# light_brick.net
KiCad netlist of a schematic drawn in EAGLE
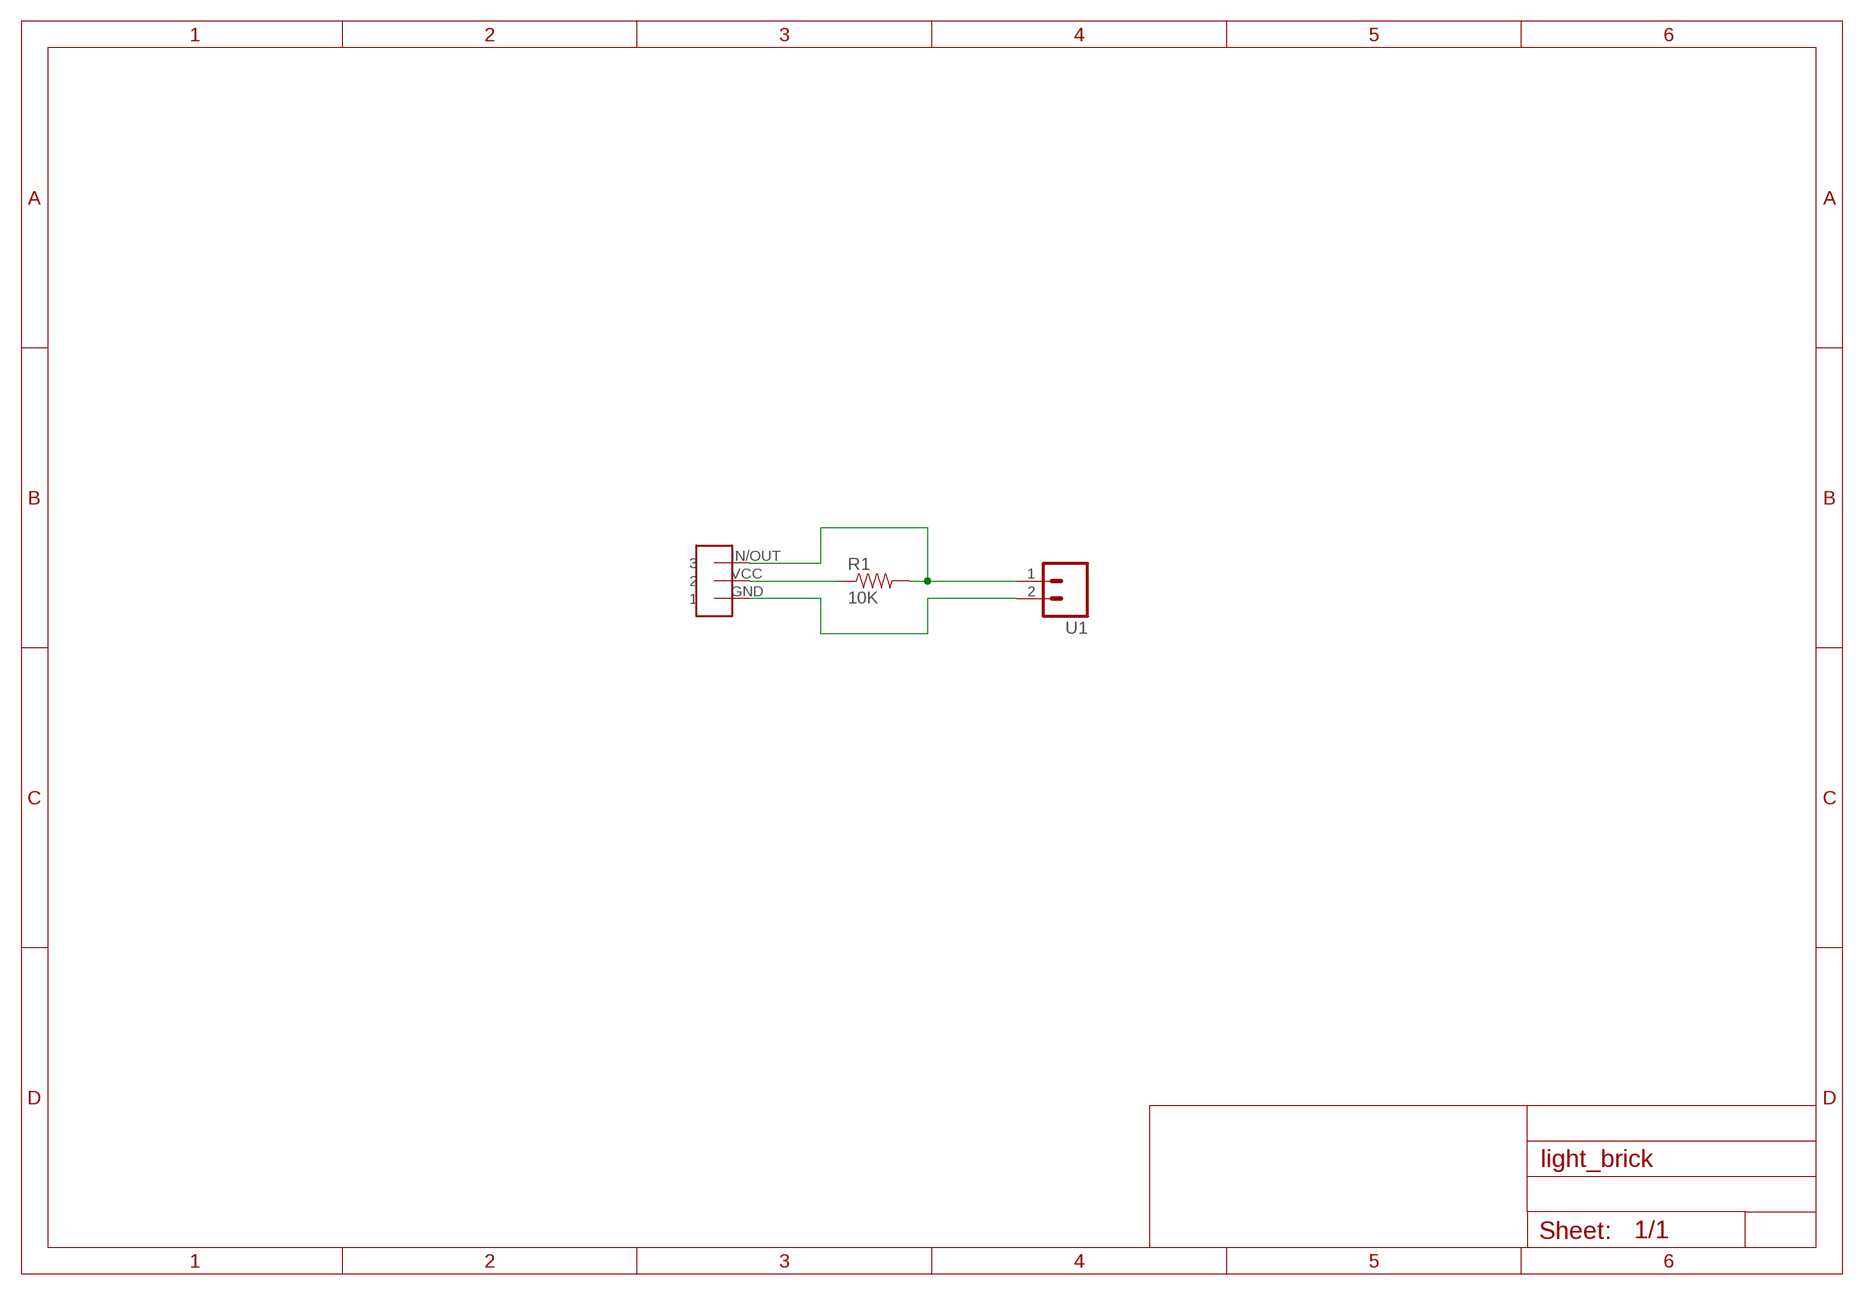
[diagram p0: schematic, sheet 1]

(export (version "E")
  (design (tool "Eeschema 10.0.6"))
  (components
    (comp (ref "R1")
      (value "10K")
      (footprint "eagle-import:AXIAL-0.3")
      (libsource (lib "eagle-import") (part "RESISTORAXIAL-0.3"))
    )
    (comp (ref "U$1")
      (value "BRICK-3PIN")
      (footprint "eagle-import:BRICK_3PIN")
      (libsource (lib "eagle-import") (part "BRICK-3PIN"))
    )
    (comp (ref "U1")
      (value "M02NG")
      (footprint "eagle-import:1X02")
      (libsource (lib "eagle-import") (part "M02NG"))
    )
  )
  (nets
    (net (code "1") (name "Net-(R1-1)") (class "Default")
      (node (ref "R1") (pin "P$1") (pinfunction "1_P$1") (pintype "passive"))
      (node (ref "U$1") (pin "VCC") (pinfunction "2_VCC") (pintype "bidirectional"))
    )
    (net (code "2") (name "Net-(R1-2)") (class "Default")
      (node (ref "R1") (pin "P$2") (pinfunction "2_P$2") (pintype "passive"))
      (node (ref "U$1") (pin "IN/OUT") (pinfunction "3_IN/OUT") (pintype "bidirectional"))
      (node (ref "U1") (pin "1") (pinfunction "1_1") (pintype "passive"))
    )
    (net (code "3") (name "Net-(U$1-1)") (class "Default")
      (node (ref "U$1") (pin "GND") (pinfunction "1_GND") (pintype "bidirectional"))
      (node (ref "U1") (pin "2") (pinfunction "2_2") (pintype "passive"))
    )
  )
)
